# FRAM.net
KiCad netlist of a schematic drawn in Altium Designer
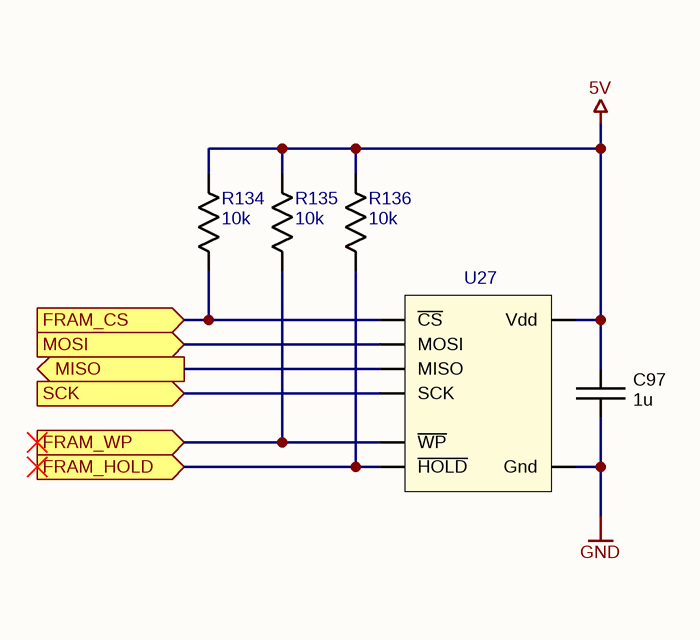
[diagram p0: FRAM.SchDoc]

(export (version "E")
  (design (tool "Eeschema 10.0.6"))
  (components
    (comp (ref "C97")
      (value "1u")
      (footprint "CAP CER 0603 NP")
      (description "CC0603KRX5R7BB105")
      (libsource (lib "levin") (part "Capacitor"))
    )
    (comp (ref "R134")
      (value "10k")
      (footprint "RES 0603")
      (description "RC0603FR-0710KL")
      (libsource (lib "levin") (part "Resistor"))
    )
    (comp (ref "R135")
      (value "10k")
      (footprint "RES 0603")
      (description "RC0603FR-0710KL")
      (libsource (lib "levin") (part "Resistor"))
    )
    (comp (ref "R136")
      (value "10k")
      (footprint "RES 0603")
      (description "RC0603FR-0710KL")
      (libsource (lib "levin") (part "Resistor"))
    )
    (comp (ref "U27")
      (value "FRAM SPI IC")
      (footprint "SOIC-8")
      (description "MB85RS64VPNF-G-JNERE1")
      (libsource (lib "levin") (part "MB85RS64V"))
    )
  )
  (nets
    (net (code "1") (name "/FRAM_CS") (class "Default")
      (node (ref "R134") (pin "1") (pinfunction "1_1") (pintype "passive"))
      (node (ref "U27") (pin "1") (pinfunction "~{CS}_1") (pintype "passive"))
    )
    (net (code "2") (name "/FRAM_HOLD") (class "Default")
      (node (ref "R136") (pin "1") (pinfunction "1_1") (pintype "passive"))
      (node (ref "U27") (pin "7") (pinfunction "~{HOLD}_7") (pintype "passive"))
    )
    (net (code "3") (name "/FRAM_WP") (class "Default")
      (node (ref "R135") (pin "1") (pinfunction "1_1") (pintype "passive"))
      (node (ref "U27") (pin "3") (pinfunction "~{WP}_3") (pintype "passive"))
    )
    (net (code "4") (name "/MISO") (class "Default")
      (node (ref "U27") (pin "2") (pinfunction "MISO_2") (pintype "passive"))
    )
    (net (code "5") (name "/MOSI") (class "Default")
      (node (ref "U27") (pin "5") (pinfunction "MOSI_5") (pintype "passive"))
    )
    (net (code "6") (name "/SCK") (class "Default")
      (node (ref "U27") (pin "6") (pinfunction "SCK_6") (pintype "passive"))
    )
    (net (code "7") (name "5V") (class "Default")
      (node (ref "C97") (pin "1") (pinfunction "1_1") (pintype "passive"))
      (node (ref "R134") (pin "2") (pinfunction "2_2") (pintype "passive"))
      (node (ref "R135") (pin "2") (pinfunction "2_2") (pintype "passive"))
      (node (ref "R136") (pin "2") (pinfunction "2_2") (pintype "passive"))
      (node (ref "U27") (pin "8") (pinfunction "Vdd_8") (pintype "passive"))
    )
    (net (code "8") (name "GND") (class "Default")
      (node (ref "C97") (pin "2") (pinfunction "2_2") (pintype "passive"))
      (node (ref "U27") (pin "4") (pinfunction "Gnd_4") (pintype "passive"))
    )
  )
)
